# QTPyNoisyBoi_PTH.net
KiCad netlist of a schematic drawn in EAGLE
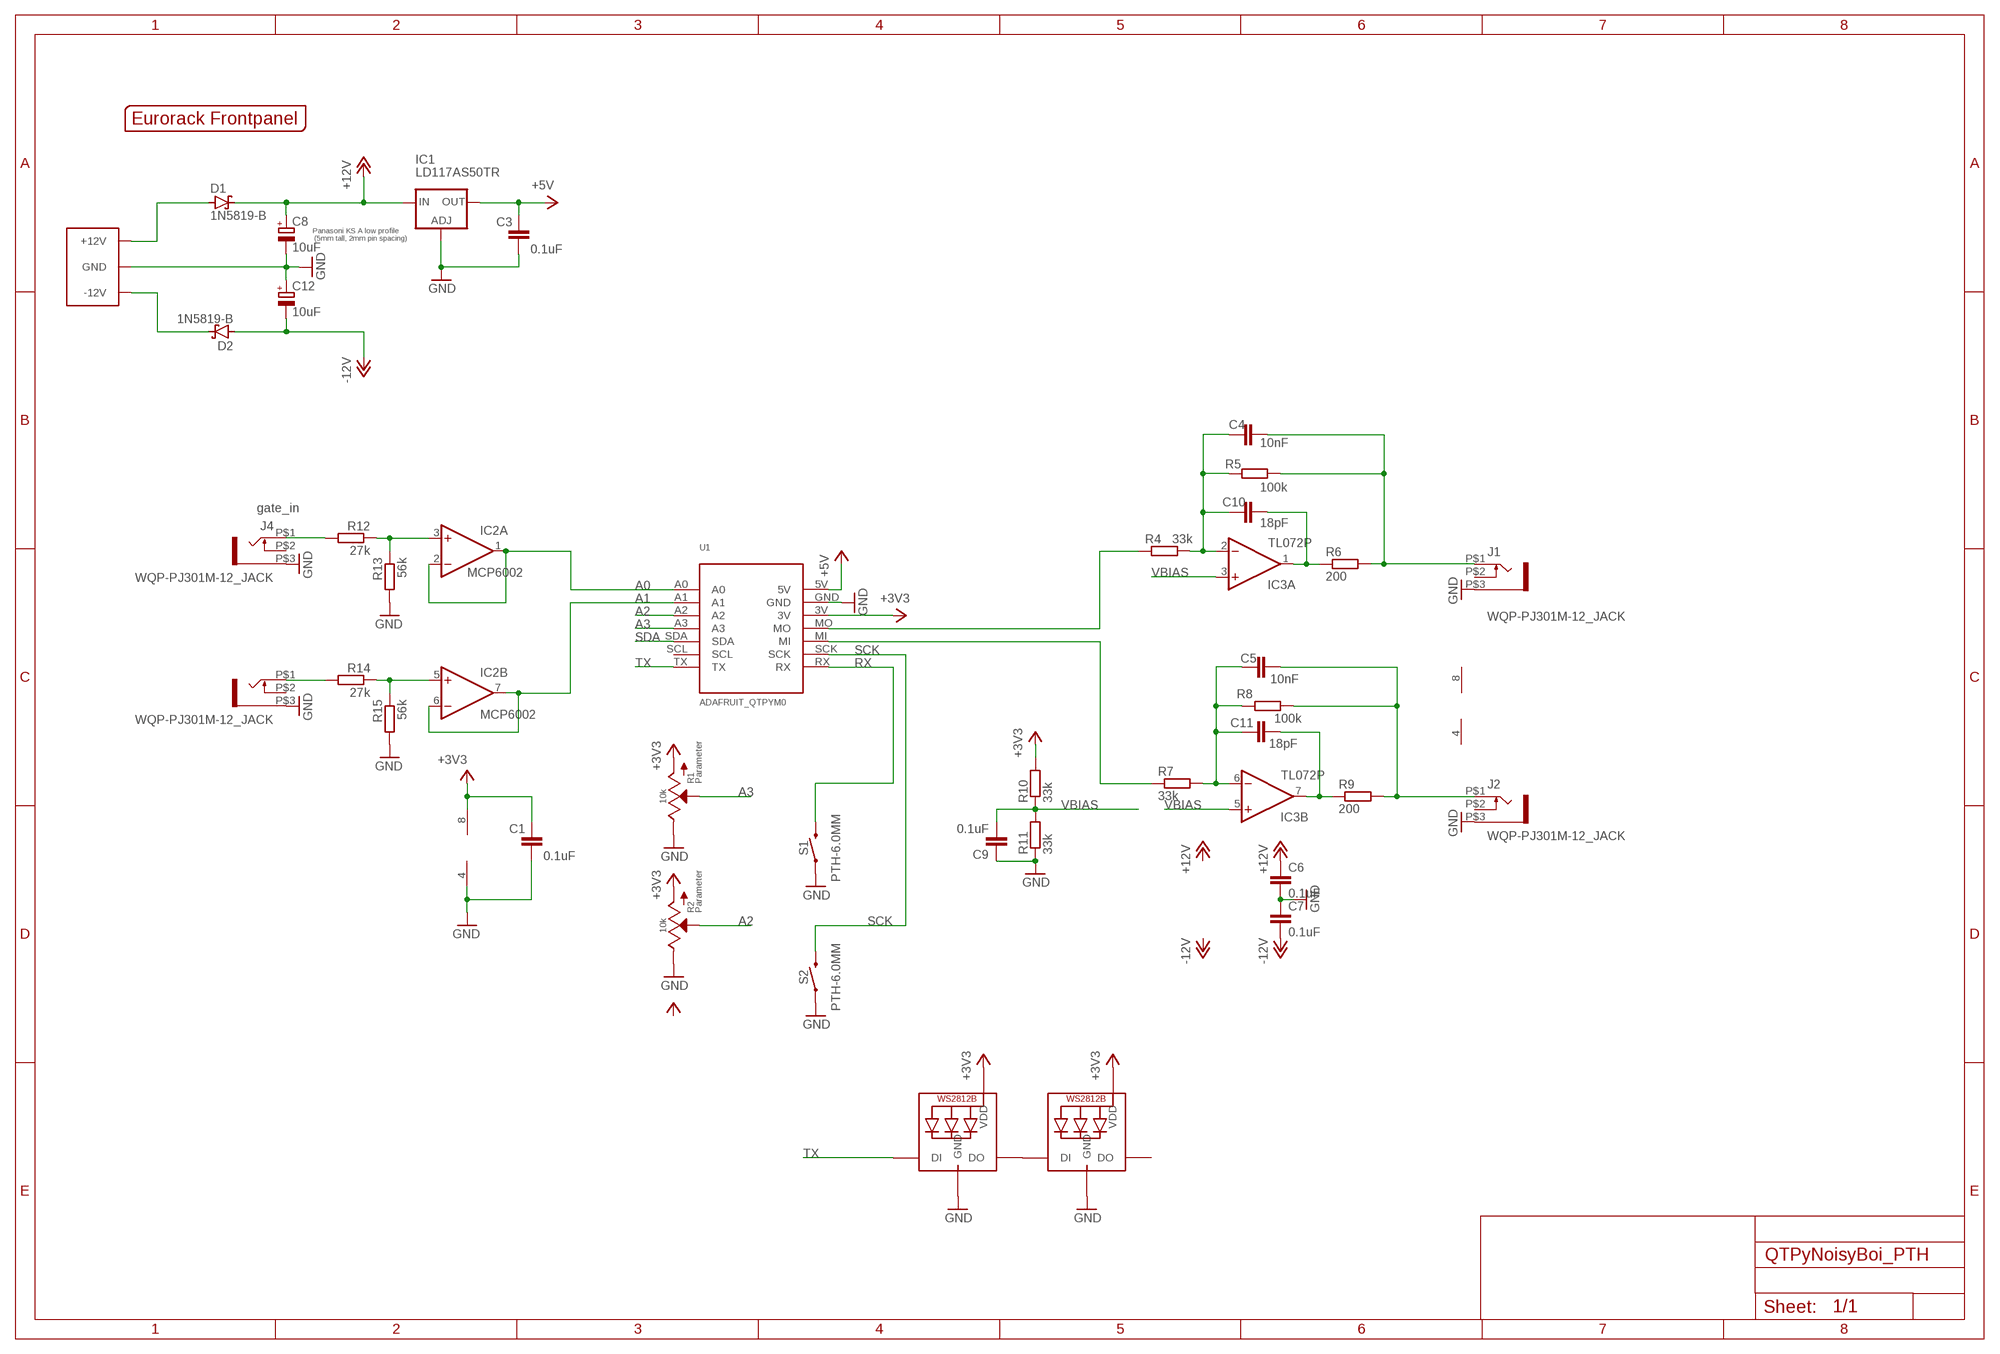
[diagram p0: schematic, sheet 1]

(export (version "E")
  (design (tool "Eeschema 10.0.6"))
  (components
    (comp (ref "C1")
      (value "0.1uF")
      (footprint "eagle-import:C025-024X044")
      (libsource (lib "eagle-import") (part "C-EU025-024X044"))
    )
    (comp (ref "C3")
      (value "0.1uF")
      (footprint "eagle-import:C025-024X044")
      (libsource (lib "eagle-import") (part "C-EU025-024X044"))
    )
    (comp (ref "C4")
      (value "10nF")
      (footprint "eagle-import:C025-024X044")
      (libsource (lib "eagle-import") (part "C-EU025-024X044"))
    )
    (comp (ref "C5")
      (value "10nF")
      (footprint "eagle-import:C025-024X044")
      (libsource (lib "eagle-import") (part "C-EU025-024X044"))
    )
    (comp (ref "C6")
      (value "0.1uF")
      (footprint "eagle-import:C025-024X044")
      (libsource (lib "eagle-import") (part "C-EU025-024X044"))
    )
    (comp (ref "C7")
      (value "0.1uF")
      (footprint "eagle-import:C025-024X044")
      (libsource (lib "eagle-import") (part "C-EU025-024X044"))
    )
    (comp (ref "C8")
      (value "10uF")
      (footprint "eagle-import:E2-5")
      (libsource (lib "eagle-import") (part "CPOL-EUE2-5"))
    )
    (comp (ref "C9")
      (value "0.1uF")
      (footprint "eagle-import:C025-024X044")
      (libsource (lib "eagle-import") (part "C-EU025-024X044"))
    )
    (comp (ref "C10")
      (value "18pF")
      (footprint "eagle-import:C025-024X044")
      (libsource (lib "eagle-import") (part "C-EU025-024X044"))
    )
    (comp (ref "C11")
      (value "18pF")
      (footprint "eagle-import:C025-024X044")
      (libsource (lib "eagle-import") (part "C-EU025-024X044"))
    )
    (comp (ref "C12")
      (value "10uF")
      (footprint "eagle-import:E2-5")
      (libsource (lib "eagle-import") (part "CPOL-EUE2-5"))
    )
    (comp (ref "D1")
      (value "1N5819-B")
      (footprint "eagle-import:DO41-7.6")
      (libsource (lib "eagle-import") (part "1N5819-B"))
    )
    (comp (ref "D2")
      (value "1N5819-B")
      (footprint "eagle-import:DO41-7.6")
      (libsource (lib "eagle-import") (part "1N5819-B"))
    )
    (comp (ref "DIM1")
      (value "EURO_POWER_LOCKSKINNY")
      (footprint "eagle-import:EURO_POWER_HEADER")
      (libsource (lib "eagle-import") (part "EURO_POWER_LOCKSKINNY"))
    )
    (comp (ref "IC1")
      (value "LD117AS50TR")
      (footprint "eagle-import:SOT223")
      (libsource (lib "eagle-import") (part "LD117A?S50TR"))
    )
    (comp (ref "IC2")
      (value "MCP6002")
      (footprint "eagle-import:DIL08")
      (libsource (lib "eagle-import") (part "TL072P"))
    )
    (comp (ref "IC3")
      (value "TL072P")
      (footprint "eagle-import:DIL08")
      (libsource (lib "eagle-import") (part "TL072P"))
    )
    (comp (ref "J1")
      (value "WQP-PJ301M-12_JACK")
      (footprint "eagle-import:WQP-PJ301M-12_JACK")
      (libsource (lib "eagle-import") (part "WQP-PJ301M-12_JACK"))
    )
    (comp (ref "J2")
      (value "WQP-PJ301M-12_JACK")
      (footprint "eagle-import:WQP-PJ301M-12_JACK")
      (libsource (lib "eagle-import") (part "WQP-PJ301M-12_JACK"))
    )
    (comp (ref "J3")
      (value "WQP-PJ301M-12_JACK")
      (footprint "eagle-import:WQP-PJ301M-12_JACK")
      (libsource (lib "eagle-import") (part "WQP-PJ301M-12_JACK"))
    )
    (comp (ref "J4")
      (value "WQP-PJ301M-12_JACK")
      (footprint "eagle-import:WQP-PJ301M-12_JACK")
      (libsource (lib "eagle-import") (part "WQP-PJ301M-12_JACK"))
    )
    (comp (ref "LED1")
      (value "WS2812B5MM_TH")
      (footprint "eagle-import:WS2812_THRUHOLE")
      (libsource (lib "eagle-import") (part "WS2812B5MM_TH"))
    )
    (comp (ref "LED2")
      (value "WS2812B5MM_TH")
      (footprint "eagle-import:WS2812_THRUHOLE")
      (libsource (lib "eagle-import") (part "WS2812B5MM_TH"))
    )
    (comp (ref "R1")
      (value "10k")
      (footprint "eagle-import:OG-POTS_ALPS_POT_VERTICAL")
      (fields (field (name "DESC") "Parameter"))
      (libsource (lib "eagle-import") (part "POTZEPHPOT"))
    )
    (comp (ref "R2")
      (value "10k")
      (footprint "eagle-import:OG-POTS_ALPS_POT_VERTICAL")
      (fields (field (name "DESC") "Parameter"))
      (libsource (lib "eagle-import") (part "POTZEPHPOT"))
    )
    (comp (ref "R4")
      (value "33k")
      (footprint "eagle-import:0204V")
      (libsource (lib "eagle-import") (part "R-EU_0204/2V"))
    )
    (comp (ref "R5")
      (value "100k")
      (footprint "eagle-import:0204V")
      (libsource (lib "eagle-import") (part "R-EU_0204/2V"))
    )
    (comp (ref "R6")
      (value "200")
      (footprint "eagle-import:0204V")
      (libsource (lib "eagle-import") (part "R-EU_0204/2V"))
    )
    (comp (ref "R7")
      (value "33k")
      (footprint "eagle-import:0204V")
      (libsource (lib "eagle-import") (part "R-EU_0204/2V"))
    )
    (comp (ref "R8")
      (value "100k")
      (footprint "eagle-import:0204V")
      (libsource (lib "eagle-import") (part "R-EU_0204/2V"))
    )
    (comp (ref "R9")
      (value "200")
      (footprint "eagle-import:0204V")
      (libsource (lib "eagle-import") (part "R-EU_0204/2V"))
    )
    (comp (ref "R10")
      (value "33k")
      (footprint "eagle-import:0204V")
      (libsource (lib "eagle-import") (part "R-EU_0204/2V"))
    )
    (comp (ref "R11")
      (value "33k")
      (footprint "eagle-import:0204V")
      (libsource (lib "eagle-import") (part "R-EU_0204/2V"))
    )
    (comp (ref "R12")
      (value "27k")
      (footprint "eagle-import:0204V")
      (libsource (lib "eagle-import") (part "R-EU_0204/2V"))
    )
    (comp (ref "R13")
      (value "56k")
      (footprint "eagle-import:0204V")
      (libsource (lib "eagle-import") (part "R-EU_0204/2V"))
    )
    (comp (ref "R14")
      (value "27k")
      (footprint "eagle-import:0204V")
      (libsource (lib "eagle-import") (part "R-EU_0204/2V"))
    )
    (comp (ref "R15")
      (value "56k")
      (footprint "eagle-import:0204V")
      (libsource (lib "eagle-import") (part "R-EU_0204/2V"))
    )
    (comp (ref "S1")
      (value "PTH-6.0MM")
      (footprint "eagle-import:TACTILE_SWITCH_PTH_6.0MM")
      (libsource (lib "eagle-import") (part "MOMENTARY-SWITCH-SPST-PTH-6.0MM"))
    )
    (comp (ref "S2")
      (value "PTH-6.0MM")
      (footprint "eagle-import:TACTILE_SWITCH_PTH_6.0MM")
      (libsource (lib "eagle-import") (part "MOMENTARY-SWITCH-SPST-PTH-6.0MM"))
    )
    (comp (ref "U$1")
      (value "EURORACK_PANEL6HP")
      (footprint "eagle-import:EURORACK6HPPANEL")
      (libsource (lib "eagle-import") (part "EURORACK_PANEL6HP"))
    )
    (comp (ref "U1")
      (value "ADAFRUIT_QTPYM0")
      (footprint "eagle-import:ADAFRUIT_QTPY_M0")
      (libsource (lib "eagle-import") (part "ADAFRUIT_QTPYM0"))
    )
  )
  (nets
    (net (code "1") (name "+3V3") (class "Default")
      (node (ref "C1") (pin "2") (pinfunction "2_2") (pintype "passive"))
      (node (ref "IC2") (pin "8") (pinfunction "V+_8") (pintype "power_in"))
      (node (ref "LED1") (pin "V") (pinfunction "VDD_V") (pintype "power_in"))
      (node (ref "LED2") (pin "V") (pinfunction "VDD_V") (pintype "power_in"))
      (node (ref "R1") (pin "P$3") (pinfunction "A_P$3") (pintype "passive"))
      (node (ref "R10") (pin "2") (pinfunction "2_2") (pintype "passive"))
      (node (ref "R2") (pin "P$3") (pinfunction "A_P$3") (pintype "passive"))
      (node (ref "U1") (pin "3V") (pinfunction "3V_3V") (pintype "bidirectional"))
    )
    (net (code "2") (name "+5V") (class "Default")
      (node (ref "C3") (pin "2") (pinfunction "2_2") (pintype "passive"))
      (node (ref "IC1") (pin "4") (pinfunction "OUT_4") (pintype "passive"))
      (node (ref "U1") (pin "5V") (pinfunction "5V_5V") (pintype "bidirectional"))
    )
    (net (code "3") (name "+12V") (class "Default")
      (node (ref "C6") (pin "1") (pinfunction "1_1") (pintype "passive"))
      (node (ref "C8") (pin "+") (pinfunction "+_+") (pintype "passive"))
      (node (ref "D1") (pin "C") (pinfunction "C_C") (pintype "passive"))
      (node (ref "IC1") (pin "3") (pinfunction "IN_3") (pintype "input"))
    )
    (net (code "4") (name "-12V") (class "Default")
      (node (ref "C12") (pin "-") (pinfunction "-_-") (pintype "passive"))
      (node (ref "C7") (pin "2") (pinfunction "2_2") (pintype "passive"))
      (node (ref "D2") (pin "A") (pinfunction "A_A") (pintype "passive"))
    )
    (net (code "5") (name "/A0") (class "Default")
      (node (ref "IC2") (pin "1") (pinfunction "OUT_1") (pintype "output"))
      (node (ref "IC2") (pin "2") (pinfunction "-IN_2") (pintype "input"))
      (node (ref "U1") (pin "A0") (pinfunction "A0_A0") (pintype "bidirectional"))
    )
    (net (code "6") (name "/A1") (class "Default")
      (node (ref "IC2") (pin "6") (pinfunction "-IN_6") (pintype "input"))
      (node (ref "IC2") (pin "7") (pinfunction "OUT_7") (pintype "output"))
      (node (ref "U1") (pin "A1") (pinfunction "A1_A1") (pintype "bidirectional"))
    )
    (net (code "7") (name "/A2") (class "Default")
      (node (ref "R2") (pin "P$2") (pinfunction "S_P$2") (pintype "passive"))
      (node (ref "U1") (pin "A2") (pinfunction "A2_A2") (pintype "bidirectional"))
    )
    (net (code "8") (name "/A3") (class "Default")
      (node (ref "R1") (pin "P$2") (pinfunction "S_P$2") (pintype "passive"))
      (node (ref "U1") (pin "A3") (pinfunction "A3_A3") (pintype "bidirectional"))
    )
    (net (code "9") (name "/RX") (class "Default")
      (node (ref "S1") (pin "3") (pinfunction "2_3") (pintype "passive"))
      (node (ref "U1") (pin "RX") (pinfunction "RX_RX") (pintype "bidirectional"))
    )
    (net (code "10") (name "/SCK") (class "Default")
      (node (ref "S2") (pin "3") (pinfunction "2_3") (pintype "passive"))
      (node (ref "U1") (pin "SCK") (pinfunction "SCK_SCK") (pintype "bidirectional"))
    )
    (net (code "11") (name "/SDA") (class "Default")
      (node (ref "U1") (pin "SDA") (pinfunction "SDA_SDA") (pintype "bidirectional"))
    )
    (net (code "12") (name "/TX") (class "Default")
      (node (ref "LED1") (pin "DI") (pinfunction "DI_DI") (pintype "input"))
      (node (ref "U1") (pin "TX") (pinfunction "TX_TX") (pintype "bidirectional"))
    )
    (net (code "13") (name "/V+") (class "Default")
      (node (ref "IC3") (pin "8") (pinfunction "V+_8") (pintype "power_in"))
    )
    (net (code "14") (name "/V-") (class "Default")
      (node (ref "IC3") (pin "4") (pinfunction "V-_4") (pintype "power_in"))
    )
    (net (code "15") (name "/VBIAS") (class "Default")
      (node (ref "C9") (pin "2") (pinfunction "2_2") (pintype "passive"))
      (node (ref "IC3") (pin "3") (pinfunction "+IN_3") (pintype "input"))
      (node (ref "IC3") (pin "5") (pinfunction "+IN_5") (pintype "input"))
      (node (ref "R10") (pin "1") (pinfunction "1_1") (pintype "passive"))
      (node (ref "R11") (pin "2") (pinfunction "2_2") (pintype "passive"))
    )
    (net (code "16") (name "GND") (class "Default")
      (node (ref "C1") (pin "1") (pinfunction "1_1") (pintype "passive"))
      (node (ref "C12") (pin "+") (pinfunction "+_+") (pintype "passive"))
      (node (ref "C3") (pin "1") (pinfunction "1_1") (pintype "passive"))
      (node (ref "C6") (pin "2") (pinfunction "2_2") (pintype "passive"))
      (node (ref "C7") (pin "1") (pinfunction "1_1") (pintype "passive"))
      (node (ref "C8") (pin "-") (pinfunction "-_-") (pintype "passive"))
      (node (ref "C9") (pin "1") (pinfunction "1_1") (pintype "passive"))
      (node (ref "DIM1") (pin "3") (pinfunction "GND_3") (pintype "bidirectional"))
      (node (ref "DIM1") (pin "4") (pinfunction "GND_4") (pintype "bidirectional"))
      (node (ref "DIM1") (pin "5") (pinfunction "GND_5") (pintype "bidirectional"))
      (node (ref "DIM1") (pin "6") (pinfunction "GND_6") (pintype "bidirectional"))
      (node (ref "DIM1") (pin "7") (pinfunction "GND_7") (pintype "bidirectional"))
      (node (ref "DIM1") (pin "8") (pinfunction "GND_8") (pintype "bidirectional"))
      (node (ref "IC1") (pin "1") (pinfunction "ADJ_1") (pintype "input"))
      (node (ref "IC2") (pin "4") (pinfunction "V-_4") (pintype "power_in"))
      (node (ref "J1") (pin "P$3") (pinfunction "1_P$3") (pintype "passive"))
      (node (ref "J2") (pin "P$3") (pinfunction "1_P$3") (pintype "passive"))
      (node (ref "J3") (pin "P$3") (pinfunction "1_P$3") (pintype "passive"))
      (node (ref "J4") (pin "P$3") (pinfunction "1_P$3") (pintype "passive"))
      (node (ref "LED1") (pin "GND") (pinfunction "GND_GND") (pintype "power_in"))
      (node (ref "LED2") (pin "GND") (pinfunction "GND_GND") (pintype "power_in"))
      (node (ref "R1") (pin "P$1") (pinfunction "E_P$1") (pintype "passive"))
      (node (ref "R11") (pin "1") (pinfunction "1_1") (pintype "passive"))
      (node (ref "R13") (pin "2") (pinfunction "2_2") (pintype "passive"))
      (node (ref "R15") (pin "2") (pinfunction "2_2") (pintype "passive"))
      (node (ref "R2") (pin "P$1") (pinfunction "E_P$1") (pintype "passive"))
      (node (ref "S1") (pin "1") (pinfunction "1_1") (pintype "passive"))
      (node (ref "S2") (pin "1") (pinfunction "1_1") (pintype "passive"))
      (node (ref "U1") (pin "GND") (pinfunction "GND_GND") (pintype "bidirectional"))
    )
    (net (code "17") (name "Net-(D1-PadA)") (class "Default")
      (node (ref "D1") (pin "A") (pinfunction "A_A") (pintype "passive"))
      (node (ref "DIM1") (pin "10") (pinfunction "+12V_10") (pintype "bidirectional"))
      (node (ref "DIM1") (pin "9") (pinfunction "+12V_9") (pintype "bidirectional"))
    )
    (net (code "18") (name "Net-(D2-PadC)") (class "Default")
      (node (ref "D2") (pin "C") (pinfunction "C_C") (pintype "passive"))
      (node (ref "DIM1") (pin "1") (pinfunction "-12V_1") (pintype "bidirectional"))
      (node (ref "DIM1") (pin "2") (pinfunction "-12V_2") (pintype "bidirectional"))
    )
    (net (code "19") (name "Net-(IC2A-+IN)") (class "Default")
      (node (ref "IC2") (pin "3") (pinfunction "+IN_3") (pintype "input"))
      (node (ref "R12") (pin "1") (pinfunction "1_1") (pintype "passive"))
      (node (ref "R13") (pin "1") (pinfunction "1_1") (pintype "passive"))
    )
    (net (code "20") (name "Net-(IC2B-+IN)") (class "Default")
      (node (ref "IC2") (pin "5") (pinfunction "+IN_5") (pintype "input"))
      (node (ref "R14") (pin "1") (pinfunction "1_1") (pintype "passive"))
      (node (ref "R15") (pin "1") (pinfunction "1_1") (pintype "passive"))
    )
    (net (code "21") (name "Net-(IC3A--IN)") (class "Default")
      (node (ref "C10") (pin "1") (pinfunction "1_1") (pintype "passive"))
      (node (ref "C4") (pin "1") (pinfunction "1_1") (pintype "passive"))
      (node (ref "IC3") (pin "2") (pinfunction "-IN_2") (pintype "input"))
      (node (ref "R4") (pin "2") (pinfunction "2_2") (pintype "passive"))
      (node (ref "R5") (pin "1") (pinfunction "1_1") (pintype "passive"))
    )
    (net (code "22") (name "Net-(IC3A-OUT)") (class "Default")
      (node (ref "C10") (pin "2") (pinfunction "2_2") (pintype "passive"))
      (node (ref "IC3") (pin "1") (pinfunction "OUT_1") (pintype "output"))
      (node (ref "R6") (pin "1") (pinfunction "1_1") (pintype "passive"))
    )
    (net (code "23") (name "Net-(IC3B--IN)") (class "Default")
      (node (ref "C11") (pin "1") (pinfunction "1_1") (pintype "passive"))
      (node (ref "C5") (pin "1") (pinfunction "1_1") (pintype "passive"))
      (node (ref "IC3") (pin "6") (pinfunction "-IN_6") (pintype "input"))
      (node (ref "R7") (pin "2") (pinfunction "2_2") (pintype "passive"))
      (node (ref "R8") (pin "1") (pinfunction "1_1") (pintype "passive"))
    )
    (net (code "24") (name "Net-(IC3B-OUT)") (class "Default")
      (node (ref "C11") (pin "2") (pinfunction "2_2") (pintype "passive"))
      (node (ref "IC3") (pin "7") (pinfunction "OUT_7") (pintype "output"))
      (node (ref "R9") (pin "1") (pinfunction "1_1") (pintype "passive"))
    )
    (net (code "25") (name "Net-(J1-2)") (class "Default")
      (node (ref "C4") (pin "2") (pinfunction "2_2") (pintype "passive"))
      (node (ref "J1") (pin "P$1") (pinfunction "2_P$1") (pintype "passive"))
      (node (ref "R5") (pin "2") (pinfunction "2_2") (pintype "passive"))
      (node (ref "R6") (pin "2") (pinfunction "2_2") (pintype "passive"))
    )
    (net (code "26") (name "Net-(J2-2)") (class "Default")
      (node (ref "C5") (pin "2") (pinfunction "2_2") (pintype "passive"))
      (node (ref "J2") (pin "P$1") (pinfunction "2_P$1") (pintype "passive"))
      (node (ref "R8") (pin "2") (pinfunction "2_2") (pintype "passive"))
      (node (ref "R9") (pin "2") (pinfunction "2_2") (pintype "passive"))
    )
    (net (code "27") (name "Net-(J3-2)") (class "Default")
      (node (ref "J3") (pin "P$1") (pinfunction "2_P$1") (pintype "passive"))
      (node (ref "R14") (pin "2") (pinfunction "2_2") (pintype "passive"))
    )
    (net (code "28") (name "Net-(J4-2)") (class "Default")
      (node (ref "J4") (pin "P$1") (pinfunction "2_P$1") (pintype "passive"))
      (node (ref "R12") (pin "2") (pinfunction "2_2") (pintype "passive"))
    )
    (net (code "29") (name "Net-(LED1-PadDO)") (class "Default")
      (node (ref "LED1") (pin "DO") (pinfunction "DO_DO") (pintype "output"))
      (node (ref "LED2") (pin "DI") (pinfunction "DI_DI") (pintype "input"))
    )
    (net (code "30") (name "Net-(R4-Pad1)") (class "Default")
      (node (ref "R4") (pin "1") (pinfunction "1_1") (pintype "passive"))
      (node (ref "U1") (pin "MO") (pinfunction "MO_MO") (pintype "bidirectional"))
    )
    (net (code "31") (name "Net-(R7-Pad1)") (class "Default")
      (node (ref "R7") (pin "1") (pinfunction "1_1") (pintype "passive"))
      (node (ref "U1") (pin "MI") (pinfunction "MI_MI") (pintype "bidirectional"))
    )
    (net (code "32") (name "unconnected-(J1-3-PadP$2)") (class "Default")
      (node (ref "J1") (pin "P$2") (pinfunction "3_P$2") (pintype "passive"))
    )
    (net (code "33") (name "unconnected-(J2-3-PadP$2)") (class "Default")
      (node (ref "J2") (pin "P$2") (pinfunction "3_P$2") (pintype "passive"))
    )
    (net (code "34") (name "unconnected-(J3-3-PadP$2)") (class "Default")
      (node (ref "J3") (pin "P$2") (pinfunction "3_P$2") (pintype "passive"))
    )
    (net (code "35") (name "unconnected-(J4-3-PadP$2)") (class "Default")
      (node (ref "J4") (pin "P$2") (pinfunction "3_P$2") (pintype "passive"))
    )
    (net (code "36") (name "unconnected-(LED2-PadDO)") (class "Default")
      (node (ref "LED2") (pin "DO") (pinfunction "DO_DO") (pintype "output"))
    )
    (net (code "37") (name "unconnected-(U1-PadSCL)") (class "Default")
      (node (ref "U1") (pin "SCL") (pinfunction "SCL_SCL") (pintype "bidirectional"))
    )
  )
)
